# old_main_board.net
KiCad netlist of a schematic drawn in EAGLE
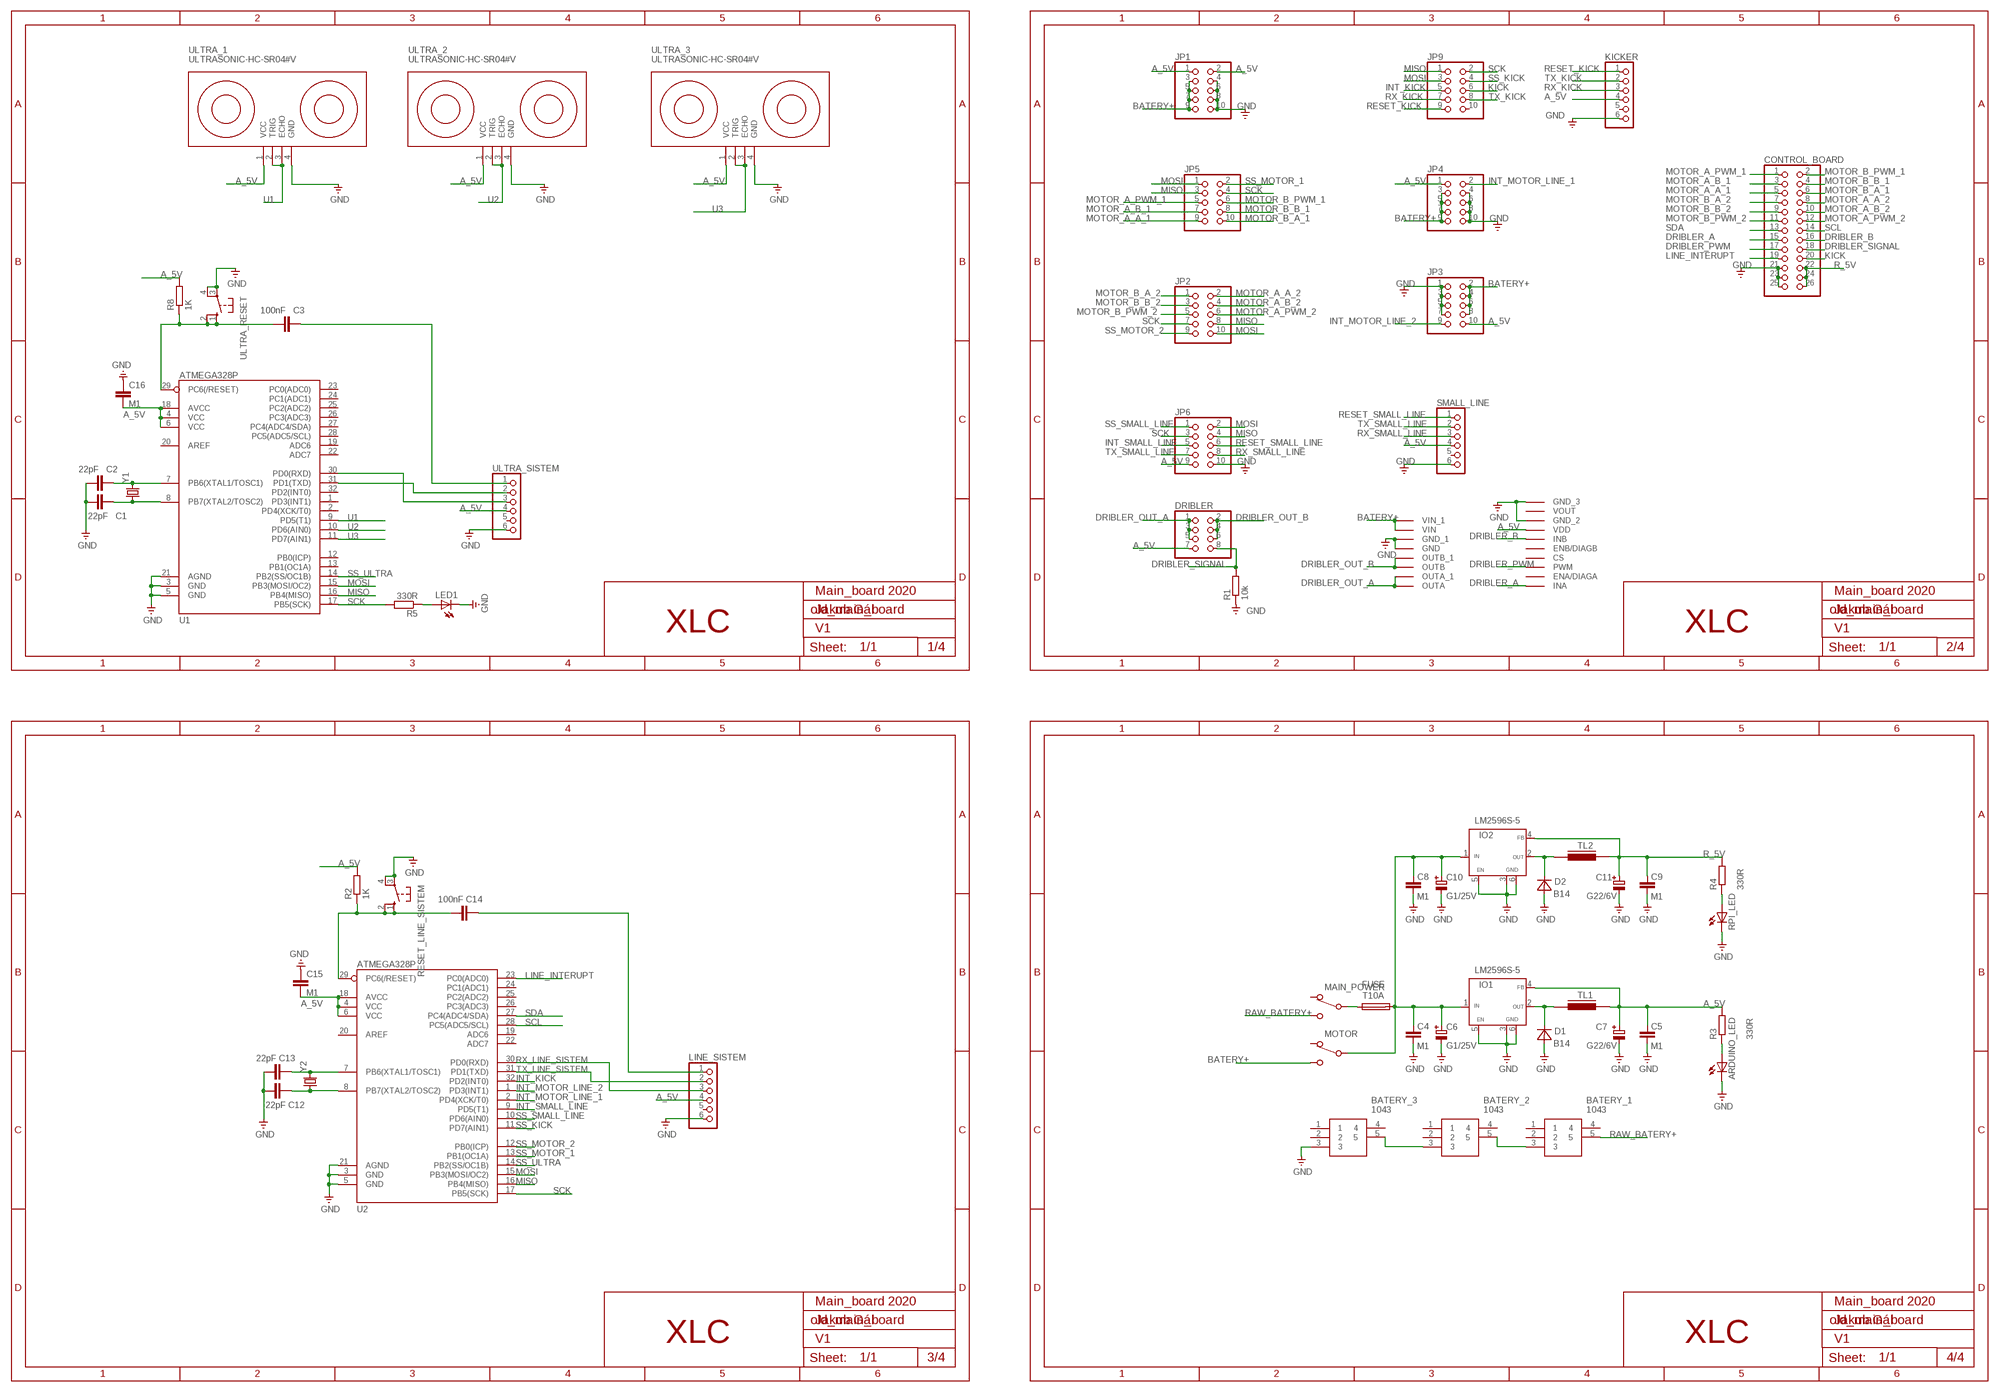
[diagram p0: schematic, sheet 1]

(export (version "E")
  (design (tool "Eeschema 10.0.6"))
  (components
    (comp (ref "ARDUINO_LED")
      (value "LEDCHIPLED_0603")
      (footprint "eagle-import:CHIPLED_0603")
      (libsource (lib "eagle-import") (part "LEDCHIPLED_0603"))
    )
    (comp (ref "BATERY_1")
      (value "1043")
      (footprint "eagle-import:1043")
      (fields (field (name "MOUSER_PART_NUMBER") "534-1043"))
      (libsource (lib "eagle-import") (part "1043"))
    )
    (comp (ref "BATERY_2")
      (value "1043")
      (footprint "eagle-import:1043")
      (fields (field (name "MOUSER_PART_NUMBER") "534-1043"))
      (libsource (lib "eagle-import") (part "1043"))
    )
    (comp (ref "BATERY_3")
      (value "1043")
      (footprint "eagle-import:1043")
      (fields (field (name "MOUSER_PART_NUMBER") "534-1043"))
      (libsource (lib "eagle-import") (part "1043"))
    )
    (comp (ref "C1")
      (value "22pF")
      (footprint "eagle-import:C0603")
      (libsource (lib "eagle-import") (part "rcl@1_C-EUC0603"))
    )
    (comp (ref "C2")
      (value "22pF")
      (footprint "eagle-import:C0603")
      (libsource (lib "eagle-import") (part "rcl@1_C-EUC0603"))
    )
    (comp (ref "C3")
      (value "100nF")
      (footprint "eagle-import:C0603")
      (libsource (lib "eagle-import") (part "rcl@1_C-EUC0603"))
    )
    (comp (ref "C4")
      (value "M1")
      (footprint "eagle-import:SMD-1206")
      (libsource (lib "eagle-import") (part "KOND-KERAM1206-SMD"))
    )
    (comp (ref "C5")
      (value "M1")
      (footprint "eagle-import:SMD-1206")
      (libsource (lib "eagle-import") (part "KOND-KERAM1206-SMD"))
    )
    (comp (ref "C6")
      (value "G1/25V")
      (footprint "eagle-import:SMD-ELE-D")
      (libsource (lib "eagle-import") (part "KOND-ELEKTD-SMD"))
    )
    (comp (ref "C7")
      (value "G22/6V")
      (footprint "eagle-import:SMD-ELE-D")
      (libsource (lib "eagle-import") (part "KOND-ELEKTD-SMD"))
    )
    (comp (ref "C8")
      (value "M1")
      (footprint "eagle-import:SMD-1206")
      (libsource (lib "eagle-import") (part "KOND-KERAM1206-SMD"))
    )
    (comp (ref "C9")
      (value "M1")
      (footprint "eagle-import:SMD-1206")
      (libsource (lib "eagle-import") (part "KOND-KERAM1206-SMD"))
    )
    (comp (ref "C10")
      (value "G1/25V")
      (footprint "eagle-import:SMD-ELE-D")
      (libsource (lib "eagle-import") (part "KOND-ELEKTD-SMD"))
    )
    (comp (ref "C11")
      (value "G22/6V")
      (footprint "eagle-import:SMD-ELE-D")
      (libsource (lib "eagle-import") (part "KOND-ELEKTD-SMD"))
    )
    (comp (ref "C12")
      (value "22pF")
      (footprint "eagle-import:C0603")
      (libsource (lib "eagle-import") (part "rcl@1_C-EUC0603"))
    )
    (comp (ref "C13")
      (value "22pF")
      (footprint "eagle-import:C0603")
      (libsource (lib "eagle-import") (part "rcl@1_C-EUC0603"))
    )
    (comp (ref "C14")
      (value "100nF")
      (footprint "eagle-import:C0603")
      (libsource (lib "eagle-import") (part "rcl@1_C-EUC0603"))
    )
    (comp (ref "C15")
      (value "M1")
      (footprint "eagle-import:C0603")
      (libsource (lib "eagle-import") (part "C-EUC0603"))
    )
    (comp (ref "C16")
      (value "M1")
      (footprint "eagle-import:C0603")
      (libsource (lib "eagle-import") (part "C-EUC0603"))
    )
    (comp (ref "CONTROL_BOARD")
      (value "PINHD-2X13_2.54")
      (footprint "eagle-import:2X13")
      (libsource (lib "eagle-import") (part "PINHD-2X13_2.54"))
    )
    (comp (ref "D1")
      (value "B14")
      (footprint "eagle-import:D-3,6X5,5")
      (libsource (lib "eagle-import") (part "DIODASMD-3,6X5,5"))
    )
    (comp (ref "D2")
      (value "B14")
      (footprint "eagle-import:D-3,6X5,5")
      (libsource (lib "eagle-import") (part "DIODASMD-3,6X5,5"))
    )
    (comp (ref "DRIBLER")
      (value "PINHD-2X4_2.54-SMD")
      (footprint "eagle-import:2X04SMD")
      (libsource (lib "eagle-import") (part "PINHD-2X4_2.54-SMD"))
    )
    (comp (ref "FUSE")
      (value "T10A")
      (footprint "eagle-import:SH22,5A")
      (libsource (lib "eagle-import") (part "POISTKA2A"))
    )
    (comp (ref "IO1")
      (value "LM2596S-5")
      (footprint "eagle-import:TO263-5")
      (libsource (lib "eagle-import") (part "LM2596S"))
    )
    (comp (ref "IO2")
      (value "LM2596S-5")
      (footprint "eagle-import:TO263-5")
      (libsource (lib "eagle-import") (part "LM2596S"))
    )
    (comp (ref "JP1")
      (value "PINHD-2X5IDC")
      (footprint "eagle-import:2X05_IDC")
      (libsource (lib "eagle-import") (part "PINHD-2X5IDC"))
    )
    (comp (ref "JP2")
      (value "PINHD-2X5IDC")
      (footprint "eagle-import:2X05_IDC")
      (libsource (lib "eagle-import") (part "PINHD-2X5IDC"))
    )
    (comp (ref "JP3")
      (value "PINHD-2X5IDC")
      (footprint "eagle-import:2X05_IDC")
      (libsource (lib "eagle-import") (part "PINHD-2X5IDC"))
    )
    (comp (ref "JP4")
      (value "PINHD-2X5IDC")
      (footprint "eagle-import:2X05_IDC")
      (libsource (lib "eagle-import") (part "PINHD-2X5IDC"))
    )
    (comp (ref "JP5")
      (value "PINHD-2X5IDC")
      (footprint "eagle-import:2X05_IDC")
      (libsource (lib "eagle-import") (part "PINHD-2X5IDC"))
    )
    (comp (ref "JP6")
      (value "PINHD-2X5IDC")
      (footprint "eagle-import:2X05_IDC")
      (libsource (lib "eagle-import") (part "PINHD-2X5IDC"))
    )
    (comp (ref "JP9")
      (value "PINHD-2X5IDC")
      (footprint "eagle-import:2X05_IDC")
      (libsource (lib "eagle-import") (part "PINHD-2X5IDC"))
    )
    (comp (ref "KICKER")
      (value "PINHD-1X6")
      (footprint "eagle-import:1X06")
      (libsource (lib "eagle-import") (part "PINHD-1X6"))
    )
    (comp (ref "LED1")
      (value "LEDCHIPLED_0603")
      (footprint "eagle-import:CHIPLED_0603")
      (libsource (lib "eagle-import") (part "LEDCHIPLED_0603"))
    )
    (comp (ref "LINE_SISTEM")
      (value "PINHD-1X6")
      (footprint "eagle-import:1X06")
      (libsource (lib "eagle-import") (part "PINHD-1X6"))
    )
    (comp (ref "MAIN_POWER")
      (value "PREP-1PB")
      (footprint "eagle-import:P-B069B")
      (libsource (lib "eagle-import") (part "PREP-1PB"))
    )
    (comp (ref "MOTOR")
      (value "PREP-1PB")
      (footprint "eagle-import:P-B069B")
      (libsource (lib "eagle-import") (part "PREP-1PB"))
    )
    (comp (ref "R1")
      (value "10k")
      (footprint "eagle-import:R0603")
      (libsource (lib "eagle-import") (part "R-EU_R0603"))
    )
    (comp (ref "R2")
      (value "1K")
      (footprint "eagle-import:R0603")
      (libsource (lib "eagle-import") (part "R-EU_R0603"))
    )
    (comp (ref "R3")
      (value "330R")
      (footprint "eagle-import:R0603")
      (libsource (lib "eagle-import") (part "R-EU_R0603"))
    )
    (comp (ref "R4")
      (value "330R")
      (footprint "eagle-import:R0603")
      (libsource (lib "eagle-import") (part "R-EU_R0603"))
    )
    (comp (ref "R5")
      (value "330R")
      (footprint "eagle-import:R0603")
      (libsource (lib "eagle-import") (part "R-EU_R0603"))
    )
    (comp (ref "R8")
      (value "1K")
      (footprint "eagle-import:R0603")
      (libsource (lib "eagle-import") (part "R-EU_R0603"))
    )
    (comp (ref "RESET_LINE_SISTEM")
      (value "10-XX")
      (footprint "eagle-import:B3F-10XX")
      (fields (field (name "MPN") "B3F-1000"))
      (libsource (lib "eagle-import") (part "10-XX"))
    )
    (comp (ref "RPI_LED")
      (value "LEDCHIPLED_0603")
      (footprint "eagle-import:CHIPLED_0603")
      (libsource (lib "eagle-import") (part "LEDCHIPLED_0603"))
    )
    (comp (ref "SMALL_LINE")
      (value "PINHD-1X6")
      (footprint "eagle-import:1X06")
      (libsource (lib "eagle-import") (part "PINHD-1X6"))
    )
    (comp (ref "TL1")
      (value "INDUK-TLSMD1")
      (footprint "eagle-import:INDUK-TL")
      (libsource (lib "eagle-import") (part "INDUK-TLSMD1"))
    )
    (comp (ref "TL2")
      (value "INDUK-TLSMD1")
      (footprint "eagle-import:INDUK-TL")
      (libsource (lib "eagle-import") (part "INDUK-TLSMD1"))
    )
    (comp (ref "U$4")
      (value "MOTOR_DRIVER")
      (footprint "eagle-import:MOTOR_DRIVER")
      (libsource (lib "eagle-import") (part "MOTOR_DRIVER"))
    )
    (comp (ref "U1")
      (value "ATMEGA328P")
      (footprint "eagle-import:TQFP32-08")
      (libsource (lib "eagle-import") (part "ATMEGA328_SMT"))
    )
    (comp (ref "U2")
      (value "ATMEGA328P")
      (footprint "eagle-import:TQFP32-08")
      (libsource (lib "eagle-import") (part "ATMEGA328_SMT"))
    )
    (comp (ref "ULTRA_1")
      (value "ULTRASONIC-HC-SR04#V")
      (footprint "eagle-import:ULTRASONIC-HC-SR04#V")
      (libsource (lib "eagle-import") (part "ULTRASONIC-HC-SR04#V"))
    )
    (comp (ref "ULTRA_2")
      (value "ULTRASONIC-HC-SR04#V")
      (footprint "eagle-import:ULTRASONIC-HC-SR04#V")
      (libsource (lib "eagle-import") (part "ULTRASONIC-HC-SR04#V"))
    )
    (comp (ref "ULTRA_3")
      (value "ULTRASONIC-HC-SR04#V")
      (footprint "eagle-import:ULTRASONIC-HC-SR04#V")
      (libsource (lib "eagle-import") (part "ULTRASONIC-HC-SR04#V"))
    )
    (comp (ref "ULTRA_RESET")
      (value "10-XX")
      (footprint "eagle-import:B3F-10XX")
      (fields (field (name "MPN") "B3F-1000"))
      (libsource (lib "eagle-import") (part "10-XX"))
    )
    (comp (ref "ULTRA_SISTEM")
      (value "PINHD-1X6")
      (footprint "eagle-import:1X06")
      (libsource (lib "eagle-import") (part "PINHD-1X6"))
    )
    (comp (ref "Y1")
      (value "CRYSTALHC49US")
      (footprint "eagle-import:HC49US")
      (libsource (lib "eagle-import") (part "CRYSTALHC49US"))
    )
    (comp (ref "Y2")
      (value "CRYSTALHC49US")
      (footprint "eagle-import:HC49US")
      (libsource (lib "eagle-import") (part "CRYSTALHC49US"))
    )
  )
  (nets
    (net (code "1") (name "/A_5V") (class "Default")
      (node (ref "C15") (pin "2") (pinfunction "2_2") (pintype "passive"))
      (node (ref "C16") (pin "2") (pinfunction "2_2") (pintype "passive"))
      (node (ref "C5") (pin "2") (pinfunction "2_2") (pintype "passive"))
      (node (ref "C7") (pin "PLUS") (pinfunction "PLUS_PLUS") (pintype "passive"))
      (node (ref "DRIBLER") (pin "7") (pinfunction "7_7") (pintype "passive"))
      (node (ref "IO1") (pin "4") (pinfunction "FB_4") (pintype "input"))
      (node (ref "JP1") (pin "1") (pinfunction "1_1") (pintype "passive"))
      (node (ref "JP1") (pin "2") (pinfunction "2_2") (pintype "passive"))
      (node (ref "JP3") (pin "10") (pinfunction "10_10") (pintype "passive"))
      (node (ref "JP4") (pin "1") (pinfunction "1_1") (pintype "passive"))
      (node (ref "JP6") (pin "9") (pinfunction "9_9") (pintype "passive"))
      (node (ref "KICKER") (pin "4") (pinfunction "4_4") (pintype "passive"))
      (node (ref "LINE_SISTEM") (pin "4") (pinfunction "4_4") (pintype "passive"))
      (node (ref "R2") (pin "2") (pinfunction "2_2") (pintype "passive"))
      (node (ref "R3") (pin "2") (pinfunction "2_2") (pintype "passive"))
      (node (ref "R8") (pin "2") (pinfunction "2_2") (pintype "passive"))
      (node (ref "SMALL_LINE") (pin "4") (pinfunction "4_4") (pintype "passive"))
      (node (ref "TL1") (pin "2") (pinfunction "2_2") (pintype "passive"))
      (node (ref "U$4") (pin "VDD") (pinfunction "VDD_VDD") (pintype "bidirectional"))
      (node (ref "U1") (pin "18") (pinfunction "AVCC_18") (pintype "bidirectional"))
      (node (ref "U1") (pin "4") (pinfunction "VCC_4") (pintype "bidirectional"))
      (node (ref "U1") (pin "6") (pinfunction "VCC_6") (pintype "bidirectional"))
      (node (ref "U2") (pin "18") (pinfunction "AVCC_18") (pintype "bidirectional"))
      (node (ref "U2") (pin "4") (pinfunction "VCC_4") (pintype "bidirectional"))
      (node (ref "U2") (pin "6") (pinfunction "VCC_6") (pintype "bidirectional"))
      (node (ref "ULTRA_1") (pin "1") (pinfunction "VCC_1") (pintype "power_in"))
      (node (ref "ULTRA_2") (pin "1") (pinfunction "VCC_1") (pintype "power_in"))
      (node (ref "ULTRA_3") (pin "1") (pinfunction "VCC_1") (pintype "power_in"))
      (node (ref "ULTRA_SISTEM") (pin "4") (pinfunction "4_4") (pintype "passive"))
    )
    (net (code "2") (name "/BATERY+") (class "Default")
      (node (ref "JP1") (pin "3") (pinfunction "3_3") (pintype "passive"))
      (node (ref "JP1") (pin "5") (pinfunction "5_5") (pintype "passive"))
      (node (ref "JP1") (pin "7") (pinfunction "7_7") (pintype "passive"))
      (node (ref "JP1") (pin "9") (pinfunction "9_9") (pintype "passive"))
      (node (ref "JP3") (pin "2") (pinfunction "2_2") (pintype "passive"))
      (node (ref "JP3") (pin "4") (pinfunction "4_4") (pintype "passive"))
      (node (ref "JP3") (pin "6") (pinfunction "6_6") (pintype "passive"))
      (node (ref "JP3") (pin "8") (pinfunction "8_8") (pintype "passive"))
      (node (ref "JP4") (pin "3") (pinfunction "3_3") (pintype "passive"))
      (node (ref "JP4") (pin "5") (pinfunction "5_5") (pintype "passive"))
      (node (ref "JP4") (pin "7") (pinfunction "7_7") (pintype "passive"))
      (node (ref "JP4") (pin "9") (pinfunction "9_9") (pintype "passive"))
      (node (ref "MOTOR") (pin "1") (pinfunction "1-OFF_1") (pintype "passive"))
      (node (ref "U$4") (pin "VIN") (pinfunction "VIN_VIN") (pintype "bidirectional"))
      (node (ref "U$4") (pin "VIN_1") (pinfunction "VIN_1_VIN_1") (pintype "bidirectional"))
    )
    (net (code "3") (name "/DRIBLER_A") (class "Default")
      (node (ref "CONTROL_BOARD") (pin "15") (pinfunction "15_15") (pintype "passive"))
      (node (ref "U$4") (pin "INA") (pinfunction "INA_INA") (pintype "bidirectional"))
    )
    (net (code "4") (name "/DRIBLER_B") (class "Default")
      (node (ref "CONTROL_BOARD") (pin "16") (pinfunction "16_16") (pintype "passive"))
      (node (ref "U$4") (pin "INB") (pinfunction "INB_INB") (pintype "bidirectional"))
    )
    (net (code "5") (name "/DRIBLER_OUT_A") (class "Default")
      (node (ref "DRIBLER") (pin "1") (pinfunction "1_1") (pintype "passive"))
      (node (ref "DRIBLER") (pin "3") (pinfunction "3_3") (pintype "passive"))
      (node (ref "DRIBLER") (pin "5") (pinfunction "5_5") (pintype "passive"))
      (node (ref "U$4") (pin "OUTA") (pinfunction "OUTA_OUTA") (pintype "bidirectional"))
      (node (ref "U$4") (pin "OUTA_1") (pinfunction "OUTA_1_OUTA_1") (pintype "bidirectional"))
    )
    (net (code "6") (name "/DRIBLER_OUT_B") (class "Default")
      (node (ref "DRIBLER") (pin "2") (pinfunction "2_2") (pintype "passive"))
      (node (ref "DRIBLER") (pin "4") (pinfunction "4_4") (pintype "passive"))
      (node (ref "DRIBLER") (pin "6") (pinfunction "6_6") (pintype "passive"))
      (node (ref "U$4") (pin "OUTB") (pinfunction "OUTB_OUTB") (pintype "bidirectional"))
      (node (ref "U$4") (pin "OUTB_1") (pinfunction "OUTB_1_OUTB_1") (pintype "bidirectional"))
    )
    (net (code "7") (name "/DRIBLER_PWM") (class "Default")
      (node (ref "CONTROL_BOARD") (pin "17") (pinfunction "17_17") (pintype "passive"))
      (node (ref "U$4") (pin "PWM") (pinfunction "PWM_PWM") (pintype "bidirectional"))
    )
    (net (code "8") (name "/DRIBLER_SIGNAL") (class "Default")
      (node (ref "CONTROL_BOARD") (pin "18") (pinfunction "18_18") (pintype "passive"))
      (node (ref "DRIBLER") (pin "8") (pinfunction "8_8") (pintype "passive"))
      (node (ref "R1") (pin "2") (pinfunction "2_2") (pintype "passive"))
    )
    (net (code "9") (name "/INT_KICK") (class "Default")
      (node (ref "JP9") (pin "5") (pinfunction "5_5") (pintype "passive"))
      (node (ref "U2") (pin "32") (pinfunction "PD2(INT0)_32") (pintype "bidirectional"))
    )
    (net (code "10") (name "/INT_MOTOR_LINE_1") (class "Default")
      (node (ref "JP4") (pin "2") (pinfunction "2_2") (pintype "passive"))
      (node (ref "U2") (pin "2") (pinfunction "PD4(XCK/T0)_2") (pintype "bidirectional"))
    )
    (net (code "11") (name "/INT_MOTOR_LINE_2") (class "Default")
      (node (ref "JP3") (pin "9") (pinfunction "9_9") (pintype "passive"))
      (node (ref "U2") (pin "1") (pinfunction "PD3(INT1)_1") (pintype "bidirectional"))
    )
    (net (code "12") (name "/INT_SMALL_LINE") (class "Default")
      (node (ref "JP6") (pin "5") (pinfunction "5_5") (pintype "passive"))
      (node (ref "U2") (pin "9") (pinfunction "PD5(T1)_9") (pintype "bidirectional"))
    )
    (net (code "13") (name "/KICK") (class "Default")
      (node (ref "CONTROL_BOARD") (pin "20") (pinfunction "20_20") (pintype "passive"))
      (node (ref "JP9") (pin "6") (pinfunction "6_6") (pintype "passive"))
    )
    (net (code "14") (name "/LINE_INTERUPT") (class "Default")
      (node (ref "CONTROL_BOARD") (pin "19") (pinfunction "19_19") (pintype "passive"))
      (node (ref "U2") (pin "23") (pinfunction "PC0(ADC0)_23") (pintype "bidirectional"))
    )
    (net (code "15") (name "/MISO") (class "Default")
      (node (ref "JP2") (pin "8") (pinfunction "8_8") (pintype "passive"))
      (node (ref "JP5") (pin "3") (pinfunction "3_3") (pintype "passive"))
      (node (ref "JP6") (pin "4") (pinfunction "4_4") (pintype "passive"))
      (node (ref "JP9") (pin "1") (pinfunction "1_1") (pintype "passive"))
      (node (ref "U1") (pin "16") (pinfunction "PB4(MISO)_16") (pintype "bidirectional"))
      (node (ref "U2") (pin "16") (pinfunction "PB4(MISO)_16") (pintype "bidirectional"))
    )
    (net (code "16") (name "/MOSI") (class "Default")
      (node (ref "JP2") (pin "10") (pinfunction "10_10") (pintype "passive"))
      (node (ref "JP5") (pin "1") (pinfunction "1_1") (pintype "passive"))
      (node (ref "JP6") (pin "2") (pinfunction "2_2") (pintype "passive"))
      (node (ref "JP9") (pin "3") (pinfunction "3_3") (pintype "passive"))
      (node (ref "U1") (pin "15") (pinfunction "PB3(MOSI/OC2)_15") (pintype "bidirectional"))
      (node (ref "U2") (pin "15") (pinfunction "PB3(MOSI/OC2)_15") (pintype "bidirectional"))
    )
    (net (code "17") (name "/MOTOR_A_A_1") (class "Default")
      (node (ref "CONTROL_BOARD") (pin "5") (pinfunction "5_5") (pintype "passive"))
      (node (ref "JP5") (pin "9") (pinfunction "9_9") (pintype "passive"))
    )
    (net (code "18") (name "/MOTOR_A_A_2") (class "Default")
      (node (ref "CONTROL_BOARD") (pin "8") (pinfunction "8_8") (pintype "passive"))
      (node (ref "JP2") (pin "2") (pinfunction "2_2") (pintype "passive"))
    )
    (net (code "19") (name "/MOTOR_A_B_1") (class "Default")
      (node (ref "CONTROL_BOARD") (pin "3") (pinfunction "3_3") (pintype "passive"))
      (node (ref "JP5") (pin "7") (pinfunction "7_7") (pintype "passive"))
    )
    (net (code "20") (name "/MOTOR_A_B_2") (class "Default")
      (node (ref "CONTROL_BOARD") (pin "10") (pinfunction "10_10") (pintype "passive"))
      (node (ref "JP2") (pin "4") (pinfunction "4_4") (pintype "passive"))
    )
    (net (code "21") (name "/MOTOR_A_PWM_1") (class "Default")
      (node (ref "CONTROL_BOARD") (pin "1") (pinfunction "1_1") (pintype "passive"))
      (node (ref "JP5") (pin "5") (pinfunction "5_5") (pintype "passive"))
    )
    (net (code "22") (name "/MOTOR_A_PWM_2") (class "Default")
      (node (ref "CONTROL_BOARD") (pin "12") (pinfunction "12_12") (pintype "passive"))
      (node (ref "JP2") (pin "6") (pinfunction "6_6") (pintype "passive"))
    )
    (net (code "23") (name "/MOTOR_B_A_1") (class "Default")
      (node (ref "CONTROL_BOARD") (pin "6") (pinfunction "6_6") (pintype "passive"))
      (node (ref "JP5") (pin "10") (pinfunction "10_10") (pintype "passive"))
    )
    (net (code "24") (name "/MOTOR_B_A_2") (class "Default")
      (node (ref "CONTROL_BOARD") (pin "7") (pinfunction "7_7") (pintype "passive"))
      (node (ref "JP2") (pin "1") (pinfunction "1_1") (pintype "passive"))
    )
    (net (code "25") (name "/MOTOR_B_B_1") (class "Default")
      (node (ref "CONTROL_BOARD") (pin "4") (pinfunction "4_4") (pintype "passive"))
      (node (ref "JP5") (pin "8") (pinfunction "8_8") (pintype "passive"))
    )
    (net (code "26") (name "/MOTOR_B_B_2") (class "Default")
      (node (ref "CONTROL_BOARD") (pin "9") (pinfunction "9_9") (pintype "passive"))
      (node (ref "JP2") (pin "3") (pinfunction "3_3") (pintype "passive"))
    )
    (net (code "27") (name "/MOTOR_B_PWM_1") (class "Default")
      (node (ref "CONTROL_BOARD") (pin "2") (pinfunction "2_2") (pintype "passive"))
      (node (ref "JP5") (pin "6") (pinfunction "6_6") (pintype "passive"))
    )
    (net (code "28") (name "/MOTOR_B_PWM_2") (class "Default")
      (node (ref "CONTROL_BOARD") (pin "11") (pinfunction "11_11") (pintype "passive"))
      (node (ref "JP2") (pin "5") (pinfunction "5_5") (pintype "passive"))
    )
    (net (code "29") (name "/RAW_BATERY+") (class "Default")
      (node (ref "BATERY_1") (pin "5") (pinfunction "5_5") (pintype "bidirectional"))
      (node (ref "MAIN_POWER") (pin "1") (pinfunction "1-OFF_1") (pintype "passive"))
    )
    (net (code "30") (name "/RESET_KICK") (class "Default")
      (node (ref "JP9") (pin "9") (pinfunction "9_9") (pintype "passive"))
      (node (ref "KICKER") (pin "1") (pinfunction "1_1") (pintype "passive"))
    )
    (net (code "31") (name "/RESET_SMALL_LINE") (class "Default")
      (node (ref "JP6") (pin "6") (pinfunction "6_6") (pintype "passive"))
      (node (ref "SMALL_LINE") (pin "1") (pinfunction "1_1") (pintype "passive"))
    )
    (net (code "32") (name "/RX_KICK") (class "Default")
      (node (ref "JP9") (pin "7") (pinfunction "7_7") (pintype "passive"))
      (node (ref "KICKER") (pin "3") (pinfunction "3_3") (pintype "passive"))
    )
    (net (code "33") (name "/RX_LINE_SISTEM") (class "Default")
      (node (ref "LINE_SISTEM") (pin "3") (pinfunction "3_3") (pintype "passive"))
      (node (ref "U2") (pin "30") (pinfunction "PD0(RXD)_30") (pintype "bidirectional"))
    )
    (net (code "34") (name "/RX_SMALL_LINE") (class "Default")
      (node (ref "JP6") (pin "8") (pinfunction "8_8") (pintype "passive"))
      (node (ref "SMALL_LINE") (pin "3") (pinfunction "3_3") (pintype "passive"))
    )
    (net (code "35") (name "/R_5V") (class "Default")
      (node (ref "C11") (pin "PLUS") (pinfunction "PLUS_PLUS") (pintype "passive"))
      (node (ref "C9") (pin "2") (pinfunction "2_2") (pintype "passive"))
      (node (ref "CONTROL_BOARD") (pin "22") (pinfunction "22_22") (pintype "passive"))
      (node (ref "CONTROL_BOARD") (pin "24") (pinfunction "24_24") (pintype "passive"))
      (node (ref "CONTROL_BOARD") (pin "26") (pinfunction "26_26") (pintype "passive"))
      (node (ref "IO2") (pin "4") (pinfunction "FB_4") (pintype "input"))
      (node (ref "R4") (pin "2") (pinfunction "2_2") (pintype "passive"))
      (node (ref "TL2") (pin "2") (pinfunction "2_2") (pintype "passive"))
    )
    (net (code "36") (name "/SCK") (class "Default")
      (node (ref "JP2") (pin "7") (pinfunction "7_7") (pintype "passive"))
      (node (ref "JP5") (pin "4") (pinfunction "4_4") (pintype "passive"))
      (node (ref "JP6") (pin "3") (pinfunction "3_3") (pintype "passive"))
      (node (ref "JP9") (pin "2") (pinfunction "2_2") (pintype "passive"))
      (node (ref "R5") (pin "2") (pinfunction "2_2") (pintype "passive"))
      (node (ref "U1") (pin "17") (pinfunction "PB5(SCK)_17") (pintype "bidirectional"))
      (node (ref "U2") (pin "17") (pinfunction "PB5(SCK)_17") (pintype "bidirectional"))
    )
    (net (code "37") (name "/SCL") (class "Default")
      (node (ref "CONTROL_BOARD") (pin "14") (pinfunction "14_14") (pintype "passive"))
      (node (ref "U2") (pin "28") (pinfunction "PC5(ADC5/SCL)_28") (pintype "bidirectional"))
    )
    (net (code "38") (name "/SDA") (class "Default")
      (node (ref "CONTROL_BOARD") (pin "13") (pinfunction "13_13") (pintype "passive"))
      (node (ref "U2") (pin "27") (pinfunction "PC4(ADC4/SDA)_27") (pintype "bidirectional"))
    )
    (net (code "39") (name "/SS_KICK") (class "Default")
      (node (ref "JP9") (pin "4") (pinfunction "4_4") (pintype "passive"))
      (node (ref "U2") (pin "11") (pinfunction "PD7(AIN1)_11") (pintype "bidirectional"))
    )
    (net (code "40") (name "/SS_MOTOR_1") (class "Default")
      (node (ref "JP5") (pin "2") (pinfunction "2_2") (pintype "passive"))
      (node (ref "U2") (pin "13") (pinfunction "PB1(OC1A)_13") (pintype "bidirectional"))
    )
    (net (code "41") (name "/SS_MOTOR_2") (class "Default")
      (node (ref "JP2") (pin "9") (pinfunction "9_9") (pintype "passive"))
      (node (ref "U2") (pin "12") (pinfunction "PB0(ICP)_12") (pintype "bidirectional"))
    )
    (net (code "42") (name "/SS_SMALL_LINE") (class "Default")
      (node (ref "JP6") (pin "1") (pinfunction "1_1") (pintype "passive"))
      (node (ref "U2") (pin "10") (pinfunction "PD6(AIN0)_10") (pintype "bidirectional"))
    )
    (net (code "43") (name "/SS_ULTRA") (class "Default")
      (node (ref "U1") (pin "14") (pinfunction "PB2(SS/OC1B)_14") (pintype "bidirectional"))
      (node (ref "U2") (pin "14") (pinfunction "PB2(SS/OC1B)_14") (pintype "bidirectional"))
    )
    (net (code "44") (name "/TX_KICK") (class "Default")
      (node (ref "JP9") (pin "8") (pinfunction "8_8") (pintype "passive"))
      (node (ref "KICKER") (pin "2") (pinfunction "2_2") (pintype "passive"))
    )
    (net (code "45") (name "/TX_LINE_SISTEM") (class "Default")
      (node (ref "LINE_SISTEM") (pin "2") (pinfunction "2_2") (pintype "passive"))
      (node (ref "U2") (pin "31") (pinfunction "PD1(TXD)_31") (pintype "bidirectional"))
    )
    (net (code "46") (name "/TX_SMALL_LINE") (class "Default")
      (node (ref "JP6") (pin "7") (pinfunction "7_7") (pintype "passive"))
      (node (ref "SMALL_LINE") (pin "2") (pinfunction "2_2") (pintype "passive"))
    )
    (net (code "47") (name "/U1") (class "Default")
      (node (ref "U1") (pin "9") (pinfunction "PD5(T1)_9") (pintype "bidirectional"))
      (node (ref "ULTRA_1") (pin "2") (pinfunction "TRIG_2") (pintype "input"))
      (node (ref "ULTRA_1") (pin "3") (pinfunction "ECHO_3") (pintype "output"))
    )
    (net (code "48") (name "/U2") (class "Default")
      (node (ref "U1") (pin "10") (pinfunction "PD6(AIN0)_10") (pintype "bidirectional"))
      (node (ref "ULTRA_2") (pin "2") (pinfunction "TRIG_2") (pintype "input"))
      (node (ref "ULTRA_2") (pin "3") (pinfunction "ECHO_3") (pintype "output"))
    )
    (net (code "49") (name "/U3") (class "Default")
      (node (ref "U1") (pin "11") (pinfunction "PD7(AIN1)_11") (pintype "bidirectional"))
      (node (ref "ULTRA_3") (pin "2") (pinfunction "TRIG_2") (pintype "input"))
      (node (ref "ULTRA_3") (pin "3") (pinfunction "ECHO_3") (pintype "output"))
    )
    (net (code "50") (name "GND") (class "Default")
      (node (ref "ARDUINO_LED") (pin "C") (pinfunction "C_C") (pintype "passive"))
      (node (ref "BATERY_3") (pin "3") (pinfunction "3_3") (pintype "bidirectional"))
      (node (ref "C1") (pin "1") (pinfunction "1_1") (pintype "passive"))
      (node (ref "C10") (pin "MINUS") (pinfunction "MINUS_MINUS") (pintype "passive"))
      (node (ref "C11") (pin "MINUS") (pinfunction "MINUS_MINUS") (pintype "passive"))
      (node (ref "C12") (pin "1") (pinfunction "1_1") (pintype "passive"))
      (node (ref "C13") (pin "1") (pinfunction "1_1") (pintype "passive"))
      (node (ref "C15") (pin "1") (pinfunction "1_1") (pintype "passive"))
      (node (ref "C16") (pin "1") (pinfunction "1_1") (pintype "passive"))
      (node (ref "C2") (pin "1") (pinfunction "1_1") (pintype "passive"))
      (node (ref "C4") (pin "1") (pinfunction "1_1") (pintype "passive"))
      (node (ref "C5") (pin "1") (pinfunction "1_1") (pintype "passive"))
      (node (ref "C6") (pin "MINUS") (pinfunction "MINUS_MINUS") (pintype "passive"))
      (node (ref "C7") (pin "MINUS") (pinfunction "MINUS_MINUS") (pintype "passive"))
      (node (ref "C8") (pin "1") (pinfunction "1_1") (pintype "passive"))
      (node (ref "C9") (pin "1") (pinfunction "1_1") (pintype "passive"))
      (node (ref "CONTROL_BOARD") (pin "21") (pinfunction "21_21") (pintype "passive"))
      (node (ref "CONTROL_BOARD") (pin "23") (pinfunction "23_23") (pintype "passive"))
      (node (ref "CONTROL_BOARD") (pin "25") (pinfunction "25_25") (pintype "passive"))
      (node (ref "D1") (pin "A") (pinfunction "A_A") (pintype "passive"))
      (node (ref "D2") (pin "A") (pinfunction "A_A") (pintype "passive"))
      (node (ref "IO1") (pin "3") (pinfunction "GND_3") (pintype "power_in"))
      (node (ref "IO1") (pin "5") (pinfunction "EN_5") (pintype "input"))
      (node (ref "IO1") (pin "6") (pinfunction "GND_6") (pintype "power_in"))
      (node (ref "IO2") (pin "3") (pinfunction "GND_3") (pintype "power_in"))
      (node (ref "IO2") (pin "5") (pinfunction "EN_5") (pintype "input"))
      (node (ref "IO2") (pin "6") (pinfunction "GND_6") (pintype "power_in"))
      (node (ref "JP1") (pin "10") (pinfunction "10_10") (pintype "passive"))
      (node (ref "JP1") (pin "4") (pinfunction "4_4") (pintype "passive"))
      (node (ref "JP1") (pin "6") (pinfunction "6_6") (pintype "passive"))
      (node (ref "JP1") (pin "8") (pinfunction "8_8") (pintype "passive"))
      (node (ref "JP3") (pin "1") (pinfunction "1_1") (pintype "passive"))
      (node (ref "JP3") (pin "3") (pinfunction "3_3") (pintype "passive"))
      (node (ref "JP3") (pin "5") (pinfunction "5_5") (pintype "passive"))
      (node (ref "JP3") (pin "7") (pinfunction "7_7") (pintype "passive"))
      (node (ref "JP4") (pin "10") (pinfunction "10_10") (pintype "passive"))
      (node (ref "JP4") (pin "4") (pinfunction "4_4") (pintype "passive"))
      (node (ref "JP4") (pin "6") (pinfunction "6_6") (pintype "passive"))
      (node (ref "JP4") (pin "8") (pinfunction "8_8") (pintype "passive"))
      (node (ref "JP6") (pin "10") (pinfunction "10_10") (pintype "passive"))
      (node (ref "KICKER") (pin "6") (pinfunction "6_6") (pintype "passive"))
      (node (ref "LED1") (pin "C") (pinfunction "C_C") (pintype "passive"))
      (node (ref "LINE_SISTEM") (pin "6") (pinfunction "6_6") (pintype "passive"))
      (node (ref "R1") (pin "1") (pinfunction "1_1") (pintype "passive"))
      (node (ref "RESET_LINE_SISTEM") (pin "3") (pinfunction "P_3") (pintype "passive"))
      (node (ref "RESET_LINE_SISTEM") (pin "4") (pinfunction "P1_4") (pintype "passive"))
      (node (ref "RPI_LED") (pin "C") (pinfunction "C_C") (pintype "passive"))
      (node (ref "SMALL_LINE") (pin "6") (pinfunction "6_6") (pintype "passive"))
      (node (ref "U$4") (pin "GND") (pinfunction "GND_GND") (pintype "bidirectional"))
      (node (ref "U$4") (pin "GND_1") (pinfunction "GND_1_GND_1") (pintype "bidirectional"))
      (node (ref "U$4") (pin "GND_2") (pinfunction "GND_2_GND_2") (pintype "bidirectional"))
      (node (ref "U$4") (pin "GND_3") (pinfunction "GND_3_GND_3") (pintype "bidirectional"))
      (node (ref "U1") (pin "21") (pinfunction "AGND_21") (pintype "bidirectional"))
      (node (ref "U1") (pin "3") (pinfunction "GND_3") (pintype "bidirectional"))
      (node (ref "U1") (pin "5") (pinfunction "GND_5") (pintype "bidirectional"))
      (node (ref "U2") (pin "21") (pinfunction "AGND_21") (pintype "bidirectional"))
      (node (ref "U2") (pin "3") (pinfunction "GND_3") (pintype "bidirectional"))
      (node (ref "U2") (pin "5") (pinfunction "GND_5") (pintype "bidirectional"))
      (node (ref "ULTRA_1") (pin "4") (pinfunction "GND_4") (pintype "power_in"))
      (node (ref "ULTRA_2") (pin "4") (pinfunction "GND_4") (pintype "power_in"))
      (node (ref "ULTRA_3") (pin "4") (pinfunction "GND_4") (pintype "power_in"))
      (node (ref "ULTRA_RESET") (pin "3") (pinfunction "P_3") (pintype "passive"))
      (node (ref "ULTRA_RESET") (pin "4") (pinfunction "P1_4") (pintype "passive"))
      (node (ref "ULTRA_SISTEM") (pin "6") (pinfunction "6_6") (pintype "passive"))
    )
    (net (code "51") (name "Net-(ARDUINO_LED-PadA)") (class "Default")
      (node (ref "ARDUINO_LED") (pin "A") (pinfunction "A_A") (pintype "passive"))
      (node (ref "R3") (pin "1") (pinfunction "1_1") (pintype "passive"))
    )
    (net (code "52") (name "Net-(BATERY_1-Pad3)") (class "Default")
      (node (ref "BATERY_1") (pin "3") (pinfunction "3_3") (pintype "bidirectional"))
      (node (ref "BATERY_2") (pin "5") (pinfunction "5_5") (pintype "bidirectional"))
    )
    (net (code "53") (name "Net-(BATERY_2-Pad3)") (class "Default")
      (node (ref "BATERY_2") (pin "3") (pinfunction "3_3") (pintype "bidirectional"))
      (node (ref "BATERY_3") (pin "5") (pinfunction "5_5") (pintype "bidirectional"))
    )
    (net (code "54") (name "Net-(C3-Pad2)") (class "Default")
      (node (ref "C3") (pin "2") (pinfunction "2_2") (pintype "passive"))
      (node (ref "ULTRA_SISTEM") (pin "1") (pinfunction "1_1") (pintype "passive"))
    )
    (net (code "55") (name "Net-(C14-Pad2)") (class "Default")
      (node (ref "C14") (pin "2") (pinfunction "2_2") (pintype "passive"))
      (node (ref "LINE_SISTEM") (pin "1") (pinfunction "1_1") (pintype "passive"))
    )
    (net (code "56") (name "Net-(IO1-IN)") (class "Default")
      (node (ref "C10") (pin "PLUS") (pinfunction "PLUS_PLUS") (pintype "passive"))
      (node (ref "C4") (pin "2") (pinfunction "2_2") (pintype "passive"))
      (node (ref "C6") (pin "PLUS") (pinfunction "PLUS_PLUS") (pintype "passive"))
      (node (ref "C8") (pin "2") (pinfunction "2_2") (pintype "passive"))
      (node (ref "FUSE") (pin "2") (pinfunction "2_2") (pintype "passive"))
      (node (ref "IO1") (pin "1") (pinfunction "IN_1") (pintype "input"))
      (node (ref "IO2") (pin "1") (pinfunction "IN_1") (pintype "input"))
      (node (ref "MOTOR") (pin "2") (pinfunction "2-COM_2") (pintype "passive"))
    )
    (net (code "57") (name "Net-(IO1-OUT)") (class "Default")
      (node (ref "D1") (pin "K") (pinfunction "K_K") (pintype "passive"))
      (node (ref "IO1") (pin "2") (pinfunction "OUT_2") (pintype "output"))
      (node (ref "TL1") (pin "1") (pinfunction "1_1") (pintype "passive"))
    )
    (net (code "58") (name "Net-(IO2-OUT)") (class "Default")
      (node (ref "D2") (pin "K") (pinfunction "K_K") (pintype "passive"))
      (node (ref "IO2") (pin "2") (pinfunction "OUT_2") (pintype "output"))
      (node (ref "TL2") (pin "1") (pinfunction "1_1") (pintype "passive"))
    )
    (net (code "59") (name "Net-(LED1-PadA)") (class "Default")
      (node (ref "LED1") (pin "A") (pinfunction "A_A") (pintype "passive"))
      (node (ref "R5") (pin "1") (pinfunction "1_1") (pintype "passive"))
    )
    (net (code "60") (name "Net-(MAIN_POWER-2-COM)") (class "Default")
      (node (ref "FUSE") (pin "1") (pinfunction "1_1") (pintype "passive"))
      (node (ref "MAIN_POWER") (pin "2") (pinfunction "2-COM_2") (pintype "passive"))
    )
    (net (code "61") (name "Net-(R4-Pad1)") (class "Default")
      (node (ref "R4") (pin "1") (pinfunction "1_1") (pintype "passive"))
      (node (ref "RPI_LED") (pin "A") (pinfunction "A_A") (pintype "passive"))
    )
    (net (code "62") (name "Net-(RESET_LINE_SISTEM-S)") (class "Default")
      (node (ref "C14") (pin "1") (pinfunction "1_1") (pintype "passive"))
      (node (ref "R2") (pin "1") (pinfunction "1_1") (pintype "passive"))
      (node (ref "RESET_LINE_SISTEM") (pin "1") (pinfunction "S_1") (pintype "passive"))
      (node (ref "RESET_LINE_SISTEM") (pin "2") (pinfunction "S1_2") (pintype "passive"))
      (node (ref "U2") (pin "29") (pinfunction "PC6(/RESET)_29") (pintype "bidirectional"))
    )
    (net (code "63") (name "Net-(U1-PB6(XTAL1{slash}TOSC1))") (class "Default")
      (node (ref "C2") (pin "2") (pinfunction "2_2") (pintype "passive"))
      (node (ref "U1") (pin "7") (pinfunction "PB6(XTAL1/TOSC1)_7") (pintype "bidirectional"))
      (node (ref "Y1") (pin "2") (pinfunction "2_2") (pintype "passive"))
    )
    (net (code "64") (name "Net-(U1-PB7(XTAL2{slash}TOSC2))") (class "Default")
      (node (ref "C1") (pin "2") (pinfunction "2_2") (pintype "passive"))
      (node (ref "U1") (pin "8") (pinfunction "PB7(XTAL2/TOSC2)_8") (pintype "bidirectional"))
      (node (ref "Y1") (pin "1") (pinfunction "1_1") (pintype "passive"))
    )
    (net (code "65") (name "Net-(U1-PC6({slash}RESET))") (class "Default")
      (node (ref "C3") (pin "1") (pinfunction "1_1") (pintype "passive"))
      (node (ref "R8") (pin "1") (pinfunction "1_1") (pintype "passive"))
      (node (ref "U1") (pin "29") (pinfunction "PC6(/RESET)_29") (pintype "bidirectional"))
      (node (ref "ULTRA_RESET") (pin "1") (pinfunction "S_1") (pintype "passive"))
      (node (ref "ULTRA_RESET") (pin "2") (pinfunction "S1_2") (pintype "passive"))
    )
    (net (code "66") (name "Net-(U1-PD0(RXD))") (class "Default")
      (node (ref "U1") (pin "30") (pinfunction "PD0(RXD)_30") (pintype "bidirectional"))
      (node (ref "ULTRA_SISTEM") (pin "3") (pinfunction "3_3") (pintype "passive"))
    )
    (net (code "67") (name "Net-(U1-PD1(TXD))") (class "Default")
      (node (ref "U1") (pin "31") (pinfunction "PD1(TXD)_31") (pintype "bidirectional"))
      (node (ref "ULTRA_SISTEM") (pin "2") (pinfunction "2_2") (pintype "passive"))
    )
    (net (code "68") (name "Net-(U2-PB6(XTAL1{slash}TOSC1))") (class "Default")
      (node (ref "C13") (pin "2") (pinfunction "2_2") (pintype "passive"))
      (node (ref "U2") (pin "7") (pinfunction "PB6(XTAL1/TOSC1)_7") (pintype "bidirectional"))
      (node (ref "Y2") (pin "2") (pinfunction "2_2") (pintype "passive"))
    )
    (net (code "69") (name "Net-(U2-PB7(XTAL2{slash}TOSC2))") (class "Default")
      (node (ref "C12") (pin "2") (pinfunction "2_2") (pintype "passive"))
      (node (ref "U2") (pin "8") (pinfunction "PB7(XTAL2/TOSC2)_8") (pintype "bidirectional"))
      (node (ref "Y2") (pin "1") (pinfunction "1_1") (pintype "passive"))
    )
    (net (code "70") (name "unconnected-(BATERY_1-Pad1)") (class "Default")
      (node (ref "BATERY_1") (pin "1") (pinfunction "1_1") (pintype "bidirectional"))
    )
    (net (code "71") (name "unconnected-(BATERY_1-Pad2)") (class "Default")
      (node (ref "BATERY_1") (pin "2") (pinfunction "2_2") (pintype "bidirectional"))
    )
    (net (code "72") (name "unconnected-(BATERY_1-Pad4)") (class "Default")
      (node (ref "BATERY_1") (pin "4") (pinfunction "4_4") (pintype "bidirectional"))
    )
    (net (code "73") (name "unconnected-(BATERY_2-Pad1)") (class "Default")
      (node (ref "BATERY_2") (pin "1") (pinfunction "1_1") (pintype "bidirectional"))
    )
    (net (code "74") (name "unconnected-(BATERY_2-Pad2)") (class "Default")
      (node (ref "BATERY_2") (pin "2") (pinfunction "2_2") (pintype "bidirectional"))
    )
    (net (code "75") (name "unconnected-(BATERY_2-Pad4)") (class "Default")
      (node (ref "BATERY_2") (pin "4") (pinfunction "4_4") (pintype "bidirectional"))
    )
    (net (code "76") (name "unconnected-(BATERY_3-Pad1)") (class "Default")
      (node (ref "BATERY_3") (pin "1") (pinfunction "1_1") (pintype "bidirectional"))
    )
    (net (code "77") (name "unconnected-(BATERY_3-Pad2)") (class "Default")
      (node (ref "BATERY_3") (pin "2") (pinfunction "2_2") (pintype "bidirectional"))
    )
    (net (code "78") (name "unconnected-(BATERY_3-Pad4)") (class "Default")
      (node (ref "BATERY_3") (pin "4") (pinfunction "4_4") (pintype "bidirectional"))
    )
    (net (code "79") (name "unconnected-(JP9-Pad10)") (class "Default")
      (node (ref "JP9") (pin "10") (pinfunction "10_10") (pintype "passive"))
    )
    (net (code "80") (name "unconnected-(KICKER-Pad5)") (class "Default")
      (node (ref "KICKER") (pin "5") (pinfunction "5_5") (pintype "passive"))
    )
    (net (code "81") (name "unconnected-(LINE_SISTEM-Pad5)") (class "Default")
      (node (ref "LINE_SISTEM") (pin "5") (pinfunction "5_5") (pintype "passive"))
    )
    (net (code "82") (name "unconnected-(MAIN_POWER-3-ON-Pad3)") (class "Default")
      (node (ref "MAIN_POWER") (pin "3") (pinfunction "3-ON_3") (pintype "passive"))
    )
    (net (code "83") (name "unconnected-(MOTOR-3-ON-Pad3)") (class "Default")
      (node (ref "MOTOR") (pin "3") (pinfunction "3-ON_3") (pintype "passive"))
    )
    (net (code "84") (name "unconnected-(SMALL_LINE-Pad5)") (class "Default")
      (node (ref "SMALL_LINE") (pin "5") (pinfunction "5_5") (pintype "passive"))
    )
    (net (code "85") (name "unconnected-(U$4-PadCS)") (class "Default")
      (node (ref "U$4") (pin "CS") (pinfunction "CS_CS") (pintype "bidirectional"))
    )
    (net (code "86") (name "unconnected-(U$4-PadENA{slash}DIAGA)") (class "Default")
      (node (ref "U$4") (pin "ENA/DIAGA") (pinfunction "ENA/DIAGA_ENA/DIAGA") (pintype "bidirectional"))
    )
    (net (code "87") (name "unconnected-(U$4-PadENB{slash}DIAGB)") (class "Default")
      (node (ref "U$4") (pin "ENB/DIAGB") (pinfunction "ENB/DIAGB_ENB/DIAGB") (pintype "bidirectional"))
    )
    (net (code "88") (name "unconnected-(U$4-PadVOUT)") (class "Default")
      (node (ref "U$4") (pin "VOUT") (pinfunction "VOUT_VOUT") (pintype "bidirectional"))
    )
    (net (code "89") (name "unconnected-(U1-ADC6-Pad19)") (class "Default")
      (node (ref "U1") (pin "19") (pinfunction "ADC6_19") (pintype "bidirectional"))
    )
    (net (code "90") (name "unconnected-(U1-ADC7-Pad22)") (class "Default")
      (node (ref "U1") (pin "22") (pinfunction "ADC7_22") (pintype "bidirectional"))
    )
    (net (code "91") (name "unconnected-(U1-AREF-Pad20)") (class "Default")
      (node (ref "U1") (pin "20") (pinfunction "AREF_20") (pintype "bidirectional"))
    )
    (net (code "92") (name "unconnected-(U1-PB0(ICP)-Pad12)") (class "Default")
      (node (ref "U1") (pin "12") (pinfunction "PB0(ICP)_12") (pintype "bidirectional"))
    )
    (net (code "93") (name "unconnected-(U1-PB1(OC1A)-Pad13)") (class "Default")
      (node (ref "U1") (pin "13") (pinfunction "PB1(OC1A)_13") (pintype "bidirectional"))
    )
    (net (code "94") (name "unconnected-(U1-PC0(ADC0)-Pad23)") (class "Default")
      (node (ref "U1") (pin "23") (pinfunction "PC0(ADC0)_23") (pintype "bidirectional"))
    )
    (net (code "95") (name "unconnected-(U1-PC1(ADC1)-Pad24)") (class "Default")
      (node (ref "U1") (pin "24") (pinfunction "PC1(ADC1)_24") (pintype "bidirectional"))
    )
    (net (code "96") (name "unconnected-(U1-PC2(ADC2)-Pad25)") (class "Default")
      (node (ref "U1") (pin "25") (pinfunction "PC2(ADC2)_25") (pintype "bidirectional"))
    )
    (net (code "97") (name "unconnected-(U1-PC3(ADC3)-Pad26)") (class "Default")
      (node (ref "U1") (pin "26") (pinfunction "PC3(ADC3)_26") (pintype "bidirectional"))
    )
    (net (code "98") (name "unconnected-(U1-PC4(ADC4{slash}SDA)-Pad27)") (class "Default")
      (node (ref "U1") (pin "27") (pinfunction "PC4(ADC4/SDA)_27") (pintype "bidirectional"))
    )
    (net (code "99") (name "unconnected-(U1-PC5(ADC5{slash}SCL)-Pad28)") (class "Default")
      (node (ref "U1") (pin "28") (pinfunction "PC5(ADC5/SCL)_28") (pintype "bidirectional"))
    )
    (net (code "100") (name "unconnected-(U1-PD2(INT0)-Pad32)") (class "Default")
      (node (ref "U1") (pin "32") (pinfunction "PD2(INT0)_32") (pintype "bidirectional"))
    )
    (net (code "101") (name "unconnected-(U1-PD3(INT1)-Pad1)") (class "Default")
      (node (ref "U1") (pin "1") (pinfunction "PD3(INT1)_1") (pintype "bidirectional"))
    )
    (net (code "102") (name "unconnected-(U1-PD4(XCK{slash}T0)-Pad2)") (class "Default")
      (node (ref "U1") (pin "2") (pinfunction "PD4(XCK/T0)_2") (pintype "bidirectional"))
    )
    (net (code "103") (name "unconnected-(U2-ADC6-Pad19)") (class "Default")
      (node (ref "U2") (pin "19") (pinfunction "ADC6_19") (pintype "bidirectional"))
    )
    (net (code "104") (name "unconnected-(U2-ADC7-Pad22)") (class "Default")
      (node (ref "U2") (pin "22") (pinfunction "ADC7_22") (pintype "bidirectional"))
    )
    (net (code "105") (name "unconnected-(U2-AREF-Pad20)") (class "Default")
      (node (ref "U2") (pin "20") (pinfunction "AREF_20") (pintype "bidirectional"))
    )
    (net (code "106") (name "unconnected-(U2-PC1(ADC1)-Pad24)") (class "Default")
      (node (ref "U2") (pin "24") (pinfunction "PC1(ADC1)_24") (pintype "bidirectional"))
    )
    (net (code "107") (name "unconnected-(U2-PC2(ADC2)-Pad25)") (class "Default")
      (node (ref "U2") (pin "25") (pinfunction "PC2(ADC2)_25") (pintype "bidirectional"))
    )
    (net (code "108") (name "unconnected-(U2-PC3(ADC3)-Pad26)") (class "Default")
      (node (ref "U2") (pin "26") (pinfunction "PC3(ADC3)_26") (pintype "bidirectional"))
    )
    (net (code "109") (name "unconnected-(ULTRA_SISTEM-Pad5)") (class "Default")
      (node (ref "ULTRA_SISTEM") (pin "5") (pinfunction "5_5") (pintype "passive"))
    )
  )
)
